# HB-UNI-Sen-WEIGHT_V1_0.net
KiCad netlist of a schematic drawn in EAGLE
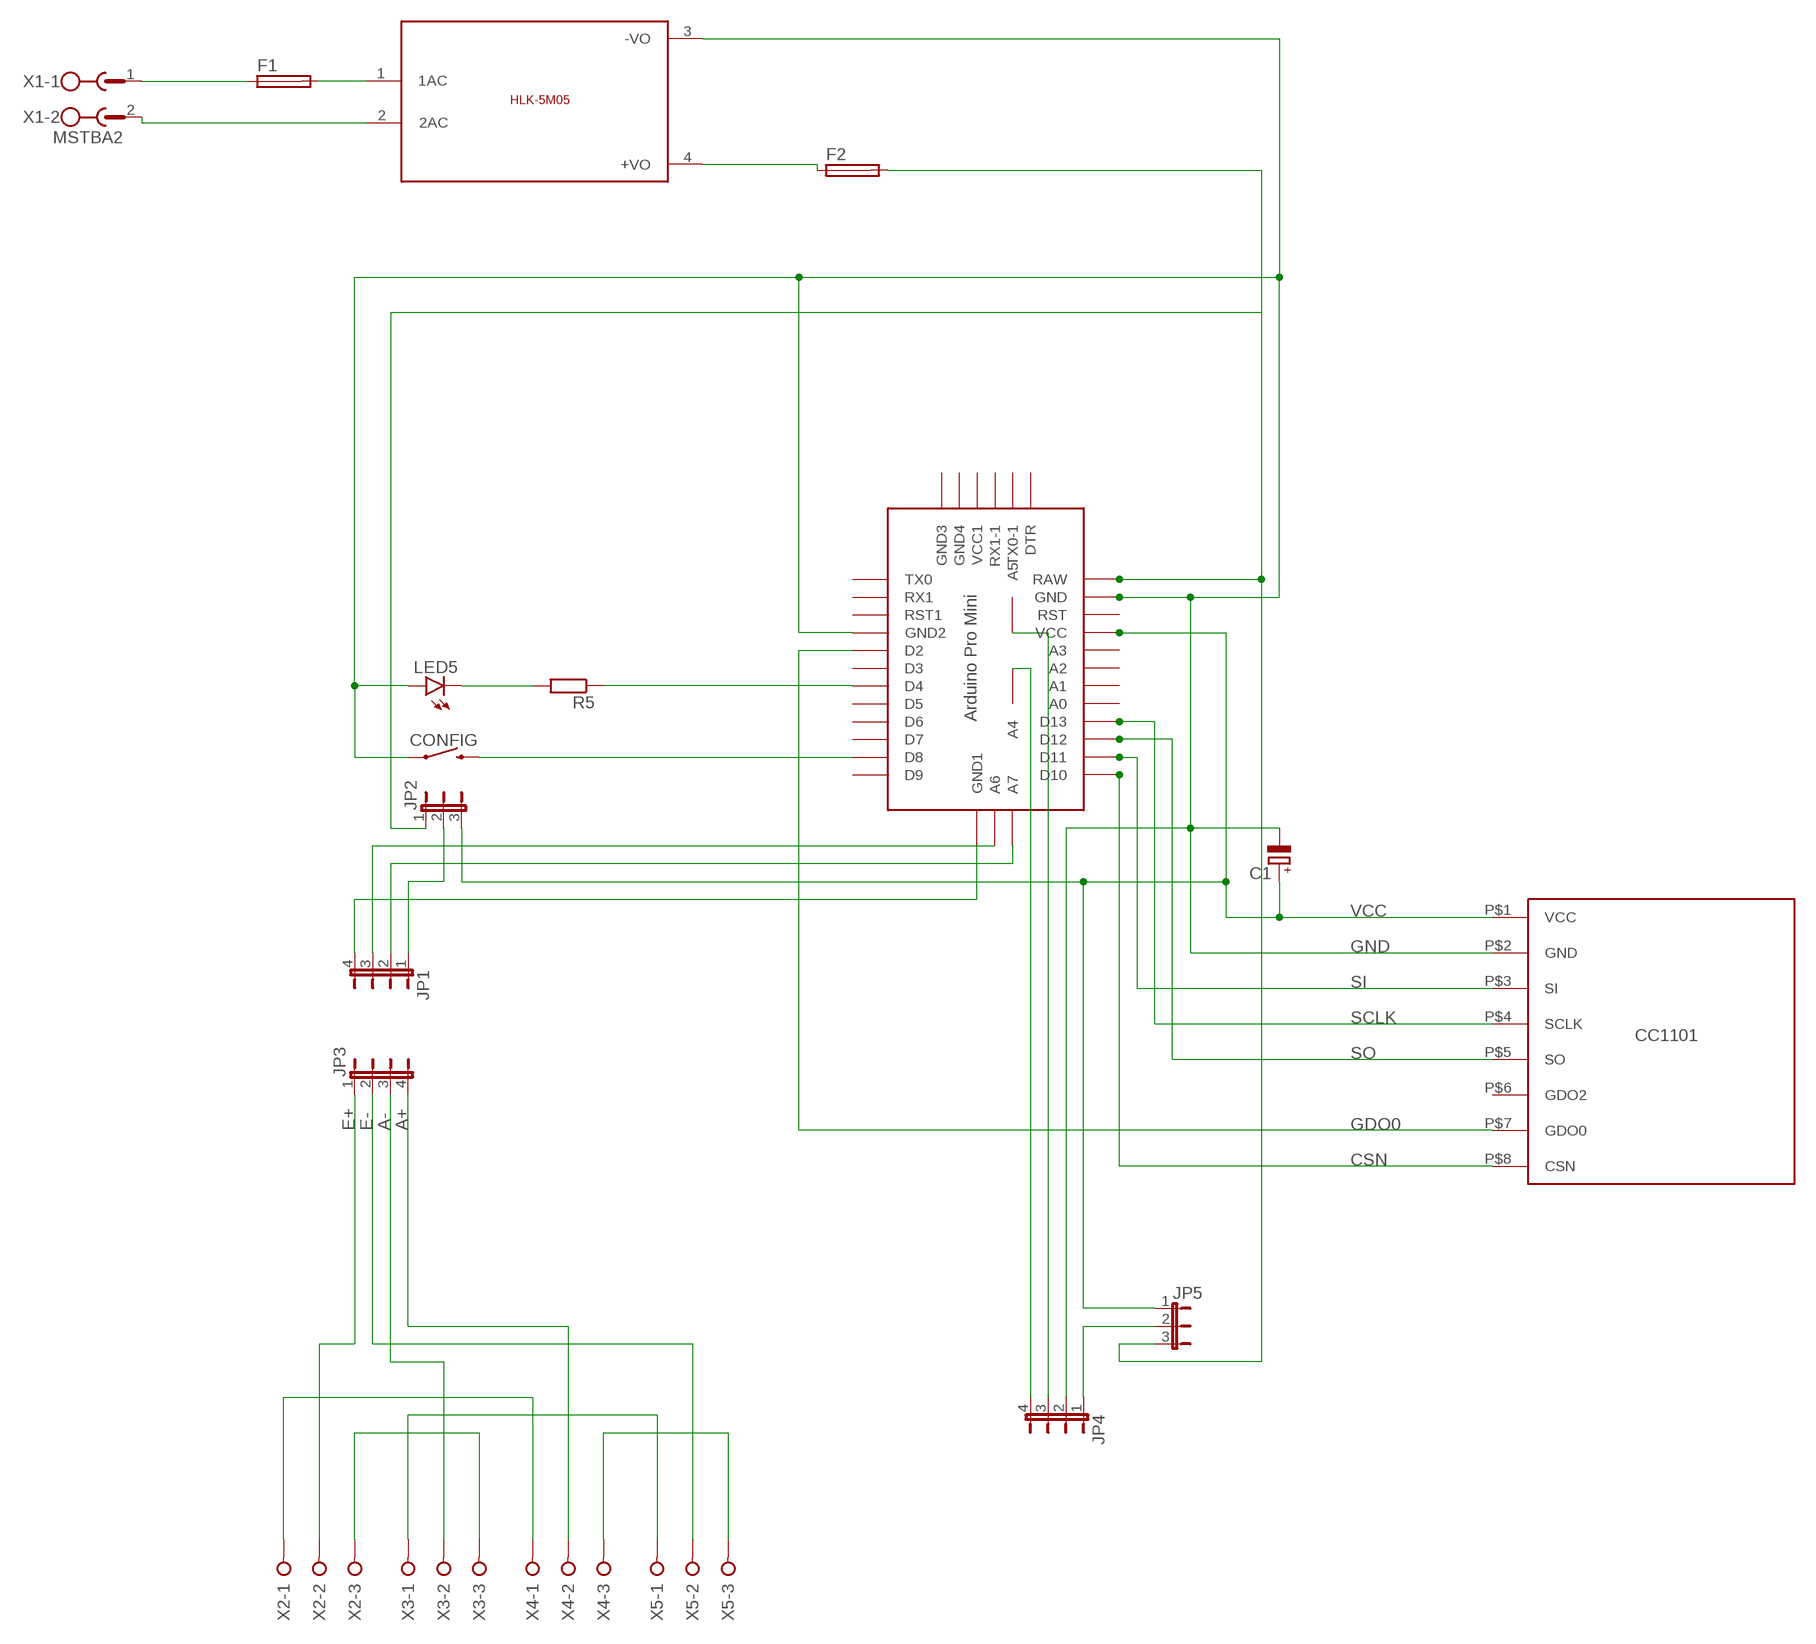
[diagram p0: schematic, sheet 1]

(export (version "E")
  (design (tool "Eeschema 10.0.6"))
  (components
    (comp (ref "C1")
      (value "CPOL-EUE2.5-5")
      (footprint "eagle-import:E2,5-5")
      (libsource (lib "eagle-import") (part "CPOL-EUE2.5-5"))
    )
    (comp (ref "CONFIG")
      (value "MOMENTARY-SWITCH-SPST-PTH-6.0MM-KIT")
      (footprint "eagle-import:TACTILE_SWITCH_PTH_6.0MM_KIT")
      (libsource (lib "eagle-import") (part "MOMENTARY-SWITCH-SPST-PTH-6.0MM-KIT"))
    )
    (comp (ref "F1")
      (value "SH22,5A")
      (footprint "eagle-import:SH22,5A")
      (fields (field (name "MPN") "0031.7701.11"))
      (libsource (lib "eagle-import") (part "SH22,5A"))
    )
    (comp (ref "F2")
      (value "SH22,5A")
      (footprint "eagle-import:SH22,5A")
      (fields (field (name "MPN") "0031.7701.11"))
      (libsource (lib "eagle-import") (part "SH22,5A"))
    )
    (comp (ref "JP1")
      (value "JP4E")
      (footprint "eagle-import:JP4")
      (libsource (lib "eagle-import") (part "JP4E"))
    )
    (comp (ref "JP2")
      (value "JP2E")
      (footprint "eagle-import:JP2")
      (libsource (lib "eagle-import") (part "JP2E"))
    )
    (comp (ref "JP3")
      (value "JP4E")
      (footprint "eagle-import:JP4")
      (libsource (lib "eagle-import") (part "JP4E"))
    )
    (comp (ref "JP4")
      (value "JP4E")
      (footprint "eagle-import:JP4")
      (libsource (lib "eagle-import") (part "JP4E"))
    )
    (comp (ref "JP5")
      (value "JP2E")
      (footprint "eagle-import:JP2")
      (libsource (lib "eagle-import") (part "JP2E"))
    )
    (comp (ref "LED5")
      (value "LED3MM")
      (footprint "eagle-import:LED3MM")
      (libsource (lib "eagle-import") (part "LED3MM"))
    )
    (comp (ref "R5")
      (value "R-EU_0309/10")
      (footprint "eagle-import:0309_10")
      (libsource (lib "eagle-import") (part "R-EU_0309/10"))
    )
    (comp (ref "U$1")
      (value "CC1101")
      (footprint "eagle-import:CC1101")
      (libsource (lib "eagle-import") (part "CC1101"))
    )
    (comp (ref "U$2")
      (value "ABK-PRO-MINI")
      (footprint "eagle-import:ABK-PRO-MINI")
      (libsource (lib "eagle-import") (part "ABK-PRO-MINI"))
    )
    (comp (ref "U$3")
      (value "5VDC/5W")
      (footprint "eagle-import:HLK-5M05")
      (libsource (lib "eagle-import") (part "HLK-5M05"))
    )
    (comp (ref "X1")
      (value "MSTBA2")
      (footprint "eagle-import:MSTBA2")
      (fields (field (name "MF") "FARNELL") (field (name "MPN") "1757242"))
      (libsource (lib "eagle-import") (part "MSTBA2"))
    )
    (comp (ref "X2")
      (value "W237-03P")
      (footprint "eagle-import:W237-133")
      (libsource (lib "eagle-import") (part "W237-03P"))
    )
    (comp (ref "X3")
      (value "W237-03P")
      (footprint "eagle-import:W237-133")
      (libsource (lib "eagle-import") (part "W237-03P"))
    )
    (comp (ref "X4")
      (value "W237-03P")
      (footprint "eagle-import:W237-133")
      (libsource (lib "eagle-import") (part "W237-03P"))
    )
    (comp (ref "X5")
      (value "W237-03P")
      (footprint "eagle-import:W237-133")
      (libsource (lib "eagle-import") (part "W237-03P"))
    )
  )
  (nets
    (net (code "1") (name "/A+") (class "Default")
      (node (ref "JP3") (pin "4") (pinfunction "4_4") (pintype "passive"))
      (node (ref "X4") (pin "2") (pinfunction "KL_2") (pintype "passive"))
    )
    (net (code "2") (name "/A-") (class "Default")
      (node (ref "JP3") (pin "3") (pinfunction "3_3") (pintype "passive"))
      (node (ref "X3") (pin "2") (pinfunction "KL_2") (pintype "passive"))
    )
    (net (code "3") (name "/CSN") (class "Default")
      (node (ref "U$1") (pin "P$8") (pinfunction "CSN_P$8") (pintype "bidirectional"))
      (node (ref "U$2") (pin "D10") (pinfunction "D10_D10") (pintype "bidirectional"))
    )
    (net (code "4") (name "/E+") (class "Default")
      (node (ref "JP3") (pin "1") (pinfunction "1_1") (pintype "passive"))
      (node (ref "X2") (pin "2") (pinfunction "KL_2") (pintype "passive"))
    )
    (net (code "5") (name "/E-") (class "Default")
      (node (ref "JP3") (pin "2") (pinfunction "2_2") (pintype "passive"))
      (node (ref "X5") (pin "2") (pinfunction "KL_2") (pintype "passive"))
    )
    (net (code "6") (name "/GDO0") (class "Default")
      (node (ref "U$1") (pin "P$7") (pinfunction "GDO0_P$7") (pintype "bidirectional"))
      (node (ref "U$2") (pin "D2") (pinfunction "D2_D2") (pintype "bidirectional"))
    )
    (net (code "7") (name "/GND") (class "Default")
      (node (ref "C1") (pin "-") (pinfunction "-_-") (pintype "passive"))
      (node (ref "CONFIG") (pin "1") (pinfunction "1_1") (pintype "passive"))
      (node (ref "JP4") (pin "2") (pinfunction "2_2") (pintype "passive"))
      (node (ref "LED5") (pin "A") (pinfunction "A_A") (pintype "passive"))
      (node (ref "U$1") (pin "P$2") (pinfunction "GND_P$2") (pintype "bidirectional"))
      (node (ref "U$2") (pin "GND") (pinfunction "GND_GND") (pintype "bidirectional"))
      (node (ref "U$2") (pin "GND1") (pinfunction "GND2_GND1") (pintype "bidirectional"))
      (node (ref "U$3") (pin "3") (pinfunction "-VO_3") (pintype "bidirectional"))
    )
    (net (code "8") (name "/SCLK") (class "Default")
      (node (ref "U$1") (pin "P$4") (pinfunction "SCLK_P$4") (pintype "bidirectional"))
      (node (ref "U$2") (pin "D13") (pinfunction "D13_D13") (pintype "bidirectional"))
    )
    (net (code "9") (name "/SI") (class "Default")
      (node (ref "U$1") (pin "P$3") (pinfunction "SI_P$3") (pintype "bidirectional"))
      (node (ref "U$2") (pin "D11") (pinfunction "D11_D11") (pintype "bidirectional"))
    )
    (net (code "10") (name "/SO") (class "Default")
      (node (ref "U$1") (pin "P$5") (pinfunction "SO_P$5") (pintype "bidirectional"))
      (node (ref "U$2") (pin "D12") (pinfunction "D12_D12") (pintype "bidirectional"))
    )
    (net (code "11") (name "/VCC") (class "Default")
      (node (ref "C1") (pin "+") (pinfunction "+_+") (pintype "passive"))
      (node (ref "JP2") (pin "3") (pinfunction "3_3") (pintype "passive"))
      (node (ref "JP5") (pin "1") (pinfunction "1_1") (pintype "passive"))
      (node (ref "U$1") (pin "P$1") (pinfunction "VCC_P$1") (pintype "bidirectional"))
      (node (ref "U$2") (pin "VCC") (pinfunction "VCC_VCC") (pintype "bidirectional"))
    )
    (net (code "12") (name "Net-(CONFIG-2)") (class "Default")
      (node (ref "CONFIG") (pin "3") (pinfunction "2_3") (pintype "passive"))
      (node (ref "U$2") (pin "D8") (pinfunction "D8_D8") (pintype "bidirectional"))
    )
    (net (code "13") (name "Net-(F1-Pad1)") (class "Default")
      (node (ref "F1") (pin "1") (pinfunction "1_1") (pintype "passive"))
      (node (ref "X1") (pin "1") (pinfunction "1_1") (pintype "passive"))
    )
    (net (code "14") (name "Net-(F2-Pad2)") (class "Default")
      (node (ref "F2") (pin "2") (pinfunction "2_2") (pintype "passive"))
      (node (ref "JP2") (pin "1") (pinfunction "1_1") (pintype "passive"))
      (node (ref "JP5") (pin "3") (pinfunction "3_3") (pintype "passive"))
      (node (ref "U$2") (pin "RAW") (pinfunction "RAW_RAW") (pintype "bidirectional"))
    )
    (net (code "15") (name "Net-(JP1-Pad1)") (class "Default")
      (node (ref "JP1") (pin "1") (pinfunction "1_1") (pintype "passive"))
      (node (ref "JP2") (pin "2") (pinfunction "2_2") (pintype "passive"))
    )
    (net (code "16") (name "Net-(JP1-Pad2)") (class "Default")
      (node (ref "JP1") (pin "2") (pinfunction "2_2") (pintype "passive"))
      (node (ref "U$2") (pin "A7") (pinfunction "A7_A7") (pintype "bidirectional"))
    )
    (net (code "17") (name "Net-(JP1-Pad3)") (class "Default")
      (node (ref "JP1") (pin "3") (pinfunction "3_3") (pintype "passive"))
      (node (ref "U$2") (pin "A6") (pinfunction "A6_A6") (pintype "bidirectional"))
    )
    (net (code "18") (name "Net-(JP4-Pad1)") (class "Default")
      (node (ref "JP4") (pin "1") (pinfunction "1_1") (pintype "passive"))
      (node (ref "JP5") (pin "2") (pinfunction "2_2") (pintype "passive"))
    )
    (net (code "19") (name "Net-(JP4-Pad3)") (class "Default")
      (node (ref "JP4") (pin "3") (pinfunction "3_3") (pintype "passive"))
      (node (ref "U$2") (pin "A5") (pinfunction "A5_A5") (pintype "bidirectional"))
    )
    (net (code "20") (name "Net-(JP4-Pad4)") (class "Default")
      (node (ref "JP4") (pin "4") (pinfunction "4_4") (pintype "passive"))
      (node (ref "U$2") (pin "A4") (pinfunction "A4_A4") (pintype "bidirectional"))
    )
    (net (code "21") (name "Net-(LED5-C)") (class "Default")
      (node (ref "LED5") (pin "K") (pinfunction "C_K") (pintype "passive"))
      (node (ref "R5") (pin "2") (pinfunction "2_2") (pintype "passive"))
    )
    (net (code "22") (name "Net-(R5-Pad1)") (class "Default")
      (node (ref "R5") (pin "1") (pinfunction "1_1") (pintype "passive"))
      (node (ref "U$2") (pin "D4") (pinfunction "D4_D4") (pintype "bidirectional"))
    )
    (net (code "23") (name "Net-(U$2-GND1)") (class "Default")
      (node (ref "JP1") (pin "4") (pinfunction "4_4") (pintype "passive"))
      (node (ref "U$2") (pin "GND4") (pinfunction "GND1_GND4") (pintype "bidirectional"))
    )
    (net (code "24") (name "Net-(U$3-+VO)") (class "Default")
      (node (ref "F2") (pin "1") (pinfunction "1_1") (pintype "passive"))
      (node (ref "U$3") (pin "4") (pinfunction "+VO_4") (pintype "bidirectional"))
    )
    (net (code "25") (name "Net-(U$3-1AC)") (class "Default")
      (node (ref "F1") (pin "2") (pinfunction "2_2") (pintype "passive"))
      (node (ref "U$3") (pin "1") (pinfunction "1AC_1") (pintype "bidirectional"))
    )
    (net (code "26") (name "Net-(U$3-2AC)") (class "Default")
      (node (ref "U$3") (pin "2") (pinfunction "2AC_2") (pintype "bidirectional"))
      (node (ref "X1") (pin "2") (pinfunction "1_2") (pintype "passive"))
    )
    (net (code "27") (name "Net-(X2A-KL)") (class "Default")
      (node (ref "X2") (pin "1") (pinfunction "KL_1") (pintype "passive"))
      (node (ref "X4") (pin "1") (pinfunction "KL_1") (pintype "passive"))
    )
    (net (code "28") (name "Net-(X2C-KL)") (class "Default")
      (node (ref "X2") (pin "3") (pinfunction "KL_3") (pintype "passive"))
      (node (ref "X3") (pin "3") (pinfunction "KL_3") (pintype "passive"))
    )
    (net (code "29") (name "Net-(X3A-KL)") (class "Default")
      (node (ref "X3") (pin "1") (pinfunction "KL_1") (pintype "passive"))
      (node (ref "X5") (pin "1") (pinfunction "KL_1") (pintype "passive"))
    )
    (net (code "30") (name "Net-(X4C-KL)") (class "Default")
      (node (ref "X4") (pin "3") (pinfunction "KL_3") (pintype "passive"))
      (node (ref "X5") (pin "3") (pinfunction "KL_3") (pintype "passive"))
    )
    (net (code "31") (name "unconnected-(U$1-GDO2-PadP$6)") (class "Default")
      (node (ref "U$1") (pin "P$6") (pinfunction "GDO2_P$6") (pintype "bidirectional"))
    )
    (net (code "32") (name "unconnected-(U$2-GND3-PadGND2)") (class "Default")
      (node (ref "U$2") (pin "GND2") (pinfunction "GND3_GND2") (pintype "bidirectional"))
    )
    (net (code "33") (name "unconnected-(U$2-GND4-PadGND3)") (class "Default")
      (node (ref "U$2") (pin "GND3") (pinfunction "GND4_GND3") (pintype "bidirectional"))
    )
    (net (code "34") (name "unconnected-(U$2-PadA0)") (class "Default")
      (node (ref "U$2") (pin "A0") (pinfunction "A0_A0") (pintype "bidirectional"))
    )
    (net (code "35") (name "unconnected-(U$2-PadA1)") (class "Default")
      (node (ref "U$2") (pin "A1") (pinfunction "A1_A1") (pintype "bidirectional"))
    )
    (net (code "36") (name "unconnected-(U$2-PadA2)") (class "Default")
      (node (ref "U$2") (pin "A2") (pinfunction "A2_A2") (pintype "bidirectional"))
    )
    (net (code "37") (name "unconnected-(U$2-PadA3)") (class "Default")
      (node (ref "U$2") (pin "A3") (pinfunction "A3_A3") (pintype "bidirectional"))
    )
    (net (code "38") (name "unconnected-(U$2-PadD3)") (class "Default")
      (node (ref "U$2") (pin "D3") (pinfunction "D3_D3") (pintype "bidirectional"))
    )
    (net (code "39") (name "unconnected-(U$2-PadD5)") (class "Default")
      (node (ref "U$2") (pin "D5") (pinfunction "D5_D5") (pintype "bidirectional"))
    )
    (net (code "40") (name "unconnected-(U$2-PadD6)") (class "Default")
      (node (ref "U$2") (pin "D6") (pinfunction "D6_D6") (pintype "bidirectional"))
    )
    (net (code "41") (name "unconnected-(U$2-PadD7)") (class "Default")
      (node (ref "U$2") (pin "D7") (pinfunction "D7_D7") (pintype "bidirectional"))
    )
    (net (code "42") (name "unconnected-(U$2-PadD9)") (class "Default")
      (node (ref "U$2") (pin "D9") (pinfunction "D9_D9") (pintype "bidirectional"))
    )
    (net (code "43") (name "unconnected-(U$2-PadDTR)") (class "Default")
      (node (ref "U$2") (pin "DTR") (pinfunction "DTR_DTR") (pintype "bidirectional"))
    )
    (net (code "44") (name "unconnected-(U$2-PadRST)") (class "Default")
      (node (ref "U$2") (pin "RST") (pinfunction "RST_RST") (pintype "bidirectional"))
    )
    (net (code "45") (name "unconnected-(U$2-PadRST1)") (class "Default")
      (node (ref "U$2") (pin "RST1") (pinfunction "RST1_RST1") (pintype "bidirectional"))
    )
    (net (code "46") (name "unconnected-(U$2-PadRX1)") (class "Default")
      (node (ref "U$2") (pin "RX1") (pinfunction "RX1_RX1") (pintype "bidirectional"))
    )
    (net (code "47") (name "unconnected-(U$2-PadRX1-1)") (class "Default")
      (node (ref "U$2") (pin "RX1-1") (pinfunction "RX1-1_RX1-1") (pintype "bidirectional"))
    )
    (net (code "48") (name "unconnected-(U$2-PadTX0)") (class "Default")
      (node (ref "U$2") (pin "TX0") (pinfunction "TX0_TX0") (pintype "bidirectional"))
    )
    (net (code "49") (name "unconnected-(U$2-PadTX0-1)") (class "Default")
      (node (ref "U$2") (pin "TX0-1") (pinfunction "TX0-1_TX0-1") (pintype "bidirectional"))
    )
    (net (code "50") (name "unconnected-(U$2-PadVCC1)") (class "Default")
      (node (ref "U$2") (pin "VCC1") (pinfunction "VCC1_VCC1") (pintype "bidirectional"))
    )
  )
)
